# PS.net
KiCad netlist of a schematic drawn in Altium Designer
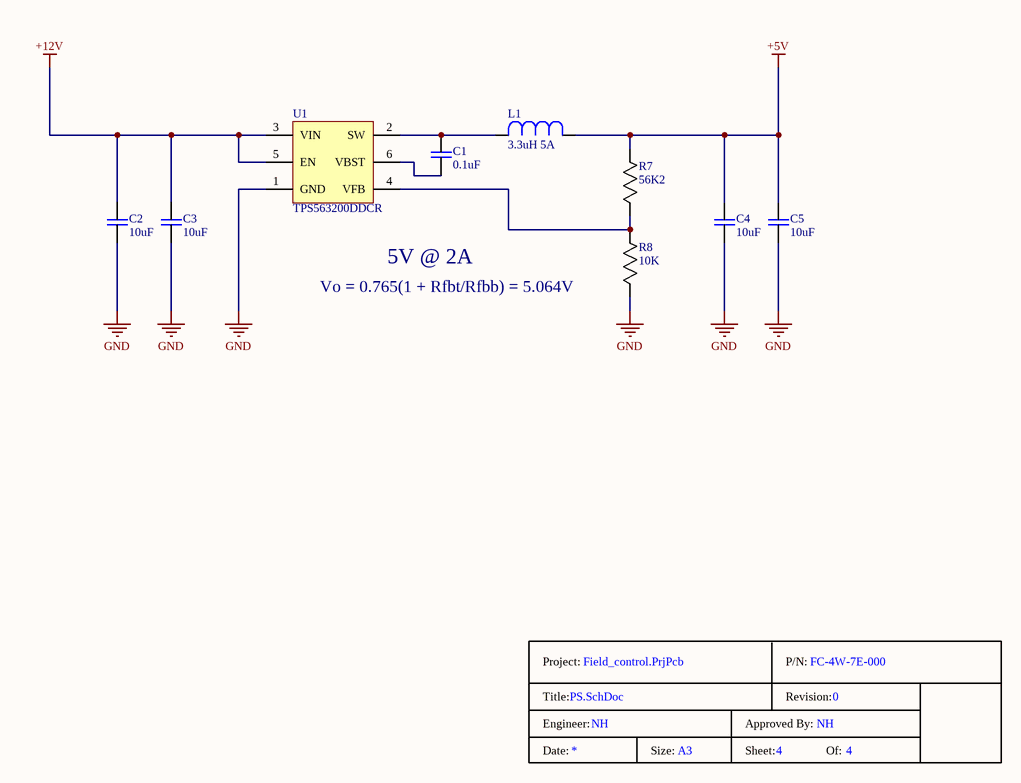
[diagram p0: PS.SchDoc]

(export (version "E")
  (design (tool "Eeschema 10.0.6"))
  (components
    (comp (ref "C1")
      (value "0.1uF")
      (footprint "C0603")
      (description "CAP CER 0.1UF 25V X7R 0603")
      (fields (field (name "MANUFACTURER") "KYOCERA AVX"))
      (libsource (lib "Capacitors") (part "KGM15BR71E104KT"))
    )
    (comp (ref "C2")
      (value "10uF")
      (footprint "C1206")
      (description "CAP CER 10UF 50V X5R 1206")
      (fields (field (name "MANUFACTURER") "Samsung Electro-Mechanics"))
      (libsource (lib "Capacitors") (part "CL31A106KBHNNNE"))
    )
    (comp (ref "C3")
      (value "10uF")
      (footprint "C1206")
      (description "CAP CER 10UF 50V X5R 1206")
      (fields (field (name "MANUFACTURER") "Samsung Electro-Mechanics"))
      (libsource (lib "Capacitors") (part "CL31A106KBHNNNE"))
    )
    (comp (ref "C4")
      (value "10uF")
      (footprint "C0603")
      (description "CAP CER 10UF 10V X5R 0603")
      (fields (field (name "MANUFACTURER") "YAGEO"))
      (libsource (lib "Capacitors") (part "CC0603MRX5R6BB106"))
    )
    (comp (ref "C5")
      (value "10uF")
      (footprint "C0603")
      (description "CAP CER 10UF 10V X5R 0603")
      (fields (field (name "MANUFACTURER") "YAGEO"))
      (libsource (lib "Capacitors") (part "CC0603MRX5R6BB106"))
    )
    (comp (ref "L1")
      (value "3.3uH 5A")
      (footprint "IHLP2020CZER3R3M01")
      (fields (field (name "MANUFACTURER") "Vishay Dale"))
      (libsource (lib "Inductor") (part "IHLP2020CZER3R3M01"))
    )
    (comp (ref "R7")
      (value "56K2")
      (footprint "R0603")
      (description "RES 56.2K OHM 1% 1/10W 0603")
      (fields (field (name "MANUFACTURER") "YAGEO"))
      (libsource (lib "Resistors") (part "RC0603FR-0756K2L"))
    )
    (comp (ref "R8")
      (value "10K")
      (footprint "R0603")
      (fields (field (name "MANUFACTURER") "Stackpole Electronics Inc"))
      (libsource (lib "Resistors") (part "RMCF0603FT10K0"))
    )
    (comp (ref "U1")
      (value "TPS563200DDCR")
      (footprint "TI-SOT23")
      (description "IC REG BUCK ADJ 3A SOT23")
      (fields (field (name "MANUFACTURER") "Texas Instruments"))
      (libsource (lib "IC") (part "TPS563200DDCR"))
    )
  )
  (nets
    (net (code "1") (name "+5V") (class "Default")
      (node (ref "C4") (pin "2") (pinfunction "2_2") (pintype "passive"))
      (node (ref "C5") (pin "2") (pinfunction "2_2") (pintype "passive"))
      (node (ref "L1") (pin "1") (pinfunction "1_1") (pintype "passive"))
      (node (ref "R7") (pin "2") (pinfunction "2_2") (pintype "passive"))
    )
    (net (code "2") (name "+12V") (class "Default")
      (node (ref "C2") (pin "2") (pinfunction "2_2") (pintype "passive"))
      (node (ref "C3") (pin "2") (pinfunction "2_2") (pintype "passive"))
      (node (ref "U1") (pin "3") (pinfunction "VIN_3") (pintype "passive"))
      (node (ref "U1") (pin "5") (pinfunction "EN_5") (pintype "passive"))
    )
    (net (code "3") (name "GND") (class "Default")
      (node (ref "C2") (pin "1") (pinfunction "1_1") (pintype "passive"))
      (node (ref "C3") (pin "1") (pinfunction "1_1") (pintype "passive"))
      (node (ref "C4") (pin "1") (pinfunction "1_1") (pintype "passive"))
      (node (ref "C5") (pin "1") (pinfunction "1_1") (pintype "passive"))
      (node (ref "R8") (pin "1") (pinfunction "1_1") (pintype "passive"))
      (node (ref "U1") (pin "1") (pinfunction "GND_1") (pintype "passive"))
    )
    (net (code "4") (name "Net-(U1-SW)") (class "Default")
      (node (ref "C1") (pin "2") (pinfunction "2_2") (pintype "passive"))
      (node (ref "L1") (pin "2") (pinfunction "2_2") (pintype "passive"))
      (node (ref "U1") (pin "2") (pinfunction "SW_2") (pintype "passive"))
    )
    (net (code "5") (name "Net-(U1-VBST)") (class "Default")
      (node (ref "C1") (pin "1") (pinfunction "1_1") (pintype "passive"))
      (node (ref "U1") (pin "6") (pinfunction "VBST_6") (pintype "passive"))
    )
    (net (code "6") (name "Net-(U1-VFB)") (class "Default")
      (node (ref "R7") (pin "1") (pinfunction "1_1") (pintype "passive"))
      (node (ref "R8") (pin "2") (pinfunction "2_2") (pintype "passive"))
      (node (ref "U1") (pin "4") (pinfunction "VFB_4") (pintype "passive"))
    )
  )
)
